# MOD-v2-5_MOD-Strips.net
KiCad netlist of a schematic drawn in EAGLE
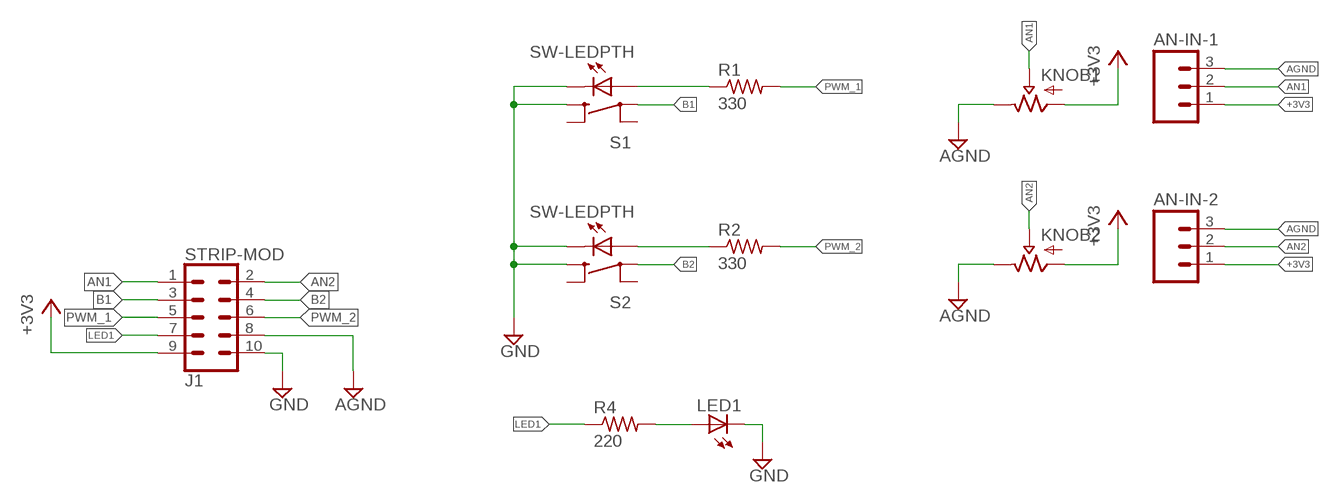
[diagram p0: schematic, sheet 1]

(export (version "E")
  (design (tool "Eeschema 10.0.6"))
  (components
    (comp (ref "AN-IN-1")
      (value "M031X03_NO_SILK")
      (footprint "eagle-import:1X03_NO_SILK")
      (libsource (lib "eagle-import") (part "M031X03_NO_SILK"))
    )
    (comp (ref "AN-IN-2")
      (value "M031X03_NO_SILK")
      (footprint "eagle-import:1X03_NO_SILK")
      (libsource (lib "eagle-import") (part "M031X03_NO_SILK"))
    )
    (comp (ref "KNOB1")
      (value "POTALPHA_RD901")
      (footprint "eagle-import:POT_ALPHA_RD901F-40-(L)R1")
      (libsource (lib "eagle-import") (part "POTALPHA_RD901"))
    )
    (comp (ref "KNOB2")
      (value "POTALPHA_RD901")
      (footprint "eagle-import:POT_ALPHA_RD901F-40-(L)R1")
      (libsource (lib "eagle-import") (part "POTALPHA_RD901"))
    )
    (comp (ref "LED1")
      (value "LED3MM")
      (footprint "eagle-import:LED3MM")
      (libsource (lib "eagle-import") (part "LED3MM"))
    )
    (comp (ref "R1")
      (value "330")
      (footprint "eagle-import:0204_7")
      (libsource (lib "eagle-import") (part "R-US_0204/7"))
    )
    (comp (ref "R2")
      (value "330")
      (footprint "eagle-import:0204_7")
      (libsource (lib "eagle-import") (part "R-US_0204/7"))
    )
    (comp (ref "R4")
      (value "220")
      (footprint "eagle-import:0204_7")
      (libsource (lib "eagle-import") (part "R-US_0204/7"))
    )
    (comp (ref "S1")
      (value "SW-LEDPTH")
      (footprint "eagle-import:SWITCH_TR2-MOMENTARY-LED")
      (libsource (lib "eagle-import") (part "SW-LEDPTH"))
    )
    (comp (ref "S2")
      (value "SW-LEDPTH")
      (footprint "eagle-import:SWITCH_TR2-MOMENTARY-LED")
      (libsource (lib "eagle-import") (part "SW-LEDPTH"))
    )
    (comp (ref "STRIP-MOD")
      (value "J1")
      (footprint "eagle-import:2X5-SHROUDED_LOCK")
      (libsource (lib "eagle-import") (part "CONN_05X2SHD_LOCK"))
    )
  )
  (nets
    (net (code "1") (name "+3V3") (class "Default")
      (node (ref "AN-IN-1") (pin "1") (pinfunction "1_1") (pintype "passive"))
      (node (ref "AN-IN-2") (pin "1") (pinfunction "1_1") (pintype "passive"))
      (node (ref "KNOB1") (pin "1") (pinfunction "IN_1") (pintype "passive"))
      (node (ref "KNOB2") (pin "1") (pinfunction "IN_1") (pintype "passive"))
      (node (ref "STRIP-MOD") (pin "9") (pinfunction "9_9") (pintype "passive"))
    )
    (net (code "2") (name "AGND") (class "Default")
      (node (ref "AN-IN-1") (pin "3") (pinfunction "3_3") (pintype "passive"))
      (node (ref "AN-IN-2") (pin "3") (pinfunction "3_3") (pintype "passive"))
      (node (ref "KNOB1") (pin "3") (pinfunction "OUT_3") (pintype "passive"))
      (node (ref "KNOB2") (pin "3") (pinfunction "OUT_3") (pintype "passive"))
      (node (ref "STRIP-MOD") (pin "8") (pinfunction "8_8") (pintype "passive"))
    )
    (net (code "3") (name "AN1") (class "Default")
      (node (ref "AN-IN-1") (pin "2") (pinfunction "2_2") (pintype "passive"))
      (node (ref "KNOB1") (pin "2") (pinfunction "WIPER_2") (pintype "passive"))
      (node (ref "STRIP-MOD") (pin "1") (pinfunction "1_1") (pintype "passive"))
    )
    (net (code "4") (name "AN2") (class "Default")
      (node (ref "AN-IN-2") (pin "2") (pinfunction "2_2") (pintype "passive"))
      (node (ref "KNOB2") (pin "2") (pinfunction "WIPER_2") (pintype "passive"))
      (node (ref "STRIP-MOD") (pin "2") (pinfunction "2_2") (pintype "passive"))
    )
    (net (code "5") (name "B1") (class "Default")
      (node (ref "S1") (pin "3") (pinfunction "3_3") (pintype "passive"))
      (node (ref "STRIP-MOD") (pin "3") (pinfunction "3_3") (pintype "passive"))
    )
    (net (code "6") (name "B2") (class "Default")
      (node (ref "S2") (pin "3") (pinfunction "3_3") (pintype "passive"))
      (node (ref "STRIP-MOD") (pin "4") (pinfunction "4_4") (pintype "passive"))
    )
    (net (code "7") (name "GND") (class "Default")
      (node (ref "LED1") (pin "K") (pinfunction "C_K") (pintype "passive"))
      (node (ref "S1") (pin "1") (pinfunction "1_1") (pintype "passive"))
      (node (ref "S1") (pin "C") (pinfunction "C_C") (pintype "passive"))
      (node (ref "S2") (pin "1") (pinfunction "1_1") (pintype "passive"))
      (node (ref "S2") (pin "C") (pinfunction "C_C") (pintype "passive"))
      (node (ref "STRIP-MOD") (pin "10") (pinfunction "10_10") (pintype "passive"))
    )
    (net (code "8") (name "LED1") (class "Default")
      (node (ref "R4") (pin "1") (pinfunction "1_1") (pintype "passive"))
      (node (ref "STRIP-MOD") (pin "7") (pinfunction "7_7") (pintype "passive"))
    )
    (net (code "9") (name "Net-(LED1-PadA)") (class "Default")
      (node (ref "LED1") (pin "A") (pinfunction "A_A") (pintype "passive"))
      (node (ref "R4") (pin "2") (pinfunction "2_2") (pintype "passive"))
    )
    (net (code "10") (name "Net-(R1-Pad1)") (class "Default")
      (node (ref "R1") (pin "1") (pinfunction "1_1") (pintype "passive"))
      (node (ref "S1") (pin "A") (pinfunction "A_A") (pintype "passive"))
    )
    (net (code "11") (name "Net-(R2-Pad1)") (class "Default")
      (node (ref "R2") (pin "1") (pinfunction "1_1") (pintype "passive"))
      (node (ref "S2") (pin "A") (pinfunction "A_A") (pintype "passive"))
    )
    (net (code "12") (name "PWM_1") (class "Default")
      (node (ref "R1") (pin "2") (pinfunction "2_2") (pintype "passive"))
      (node (ref "STRIP-MOD") (pin "5") (pinfunction "5_5") (pintype "passive"))
    )
    (net (code "13") (name "PWM_2") (class "Default")
      (node (ref "R2") (pin "2") (pinfunction "2_2") (pintype "passive"))
      (node (ref "STRIP-MOD") (pin "6") (pinfunction "6_6") (pintype "passive"))
    )
    (net (code "14") (name "unconnected-(S1-Pad2)") (class "Default")
      (node (ref "S1") (pin "2") (pinfunction "2_2") (pintype "passive"))
    )
    (net (code "15") (name "unconnected-(S1-Pad4)") (class "Default")
      (node (ref "S1") (pin "4") (pinfunction "4_4") (pintype "passive"))
    )
    (net (code "16") (name "unconnected-(S2-Pad2)") (class "Default")
      (node (ref "S2") (pin "2") (pinfunction "2_2") (pintype "passive"))
    )
    (net (code "17") (name "unconnected-(S2-Pad4)") (class "Default")
      (node (ref "S2") (pin "4") (pinfunction "4_4") (pintype "passive"))
    )
  )
)
